# USB_OTG_FS.net
KiCad netlist of a schematic drawn in Altium Designer
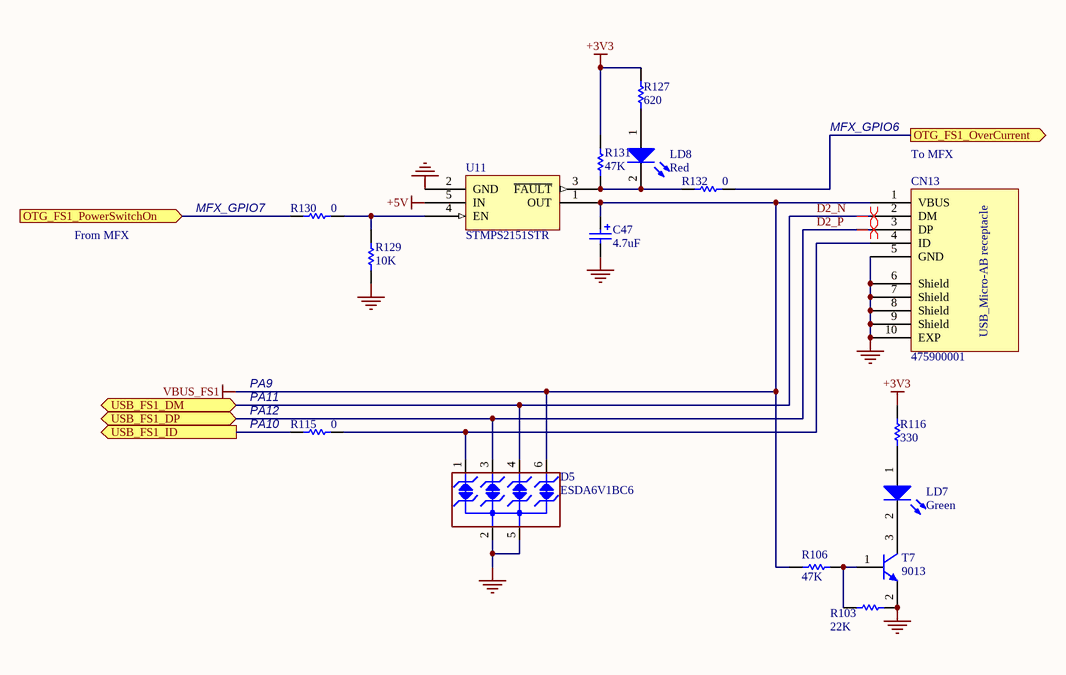
[diagram p0: USB_OTG_FS.SchDoc]

(export (version "E")
  (design (tool "Eeschema 10.0.6"))
  (components
    (comp (ref "C47")
      (value "4.7uF")
      (footprint "TAN-A")
      (description "Polarized Capacitor (Radial)")
      (fields (field (name "PUBLISHER") "Altium Limited"))
      (libsource (lib "Miscellaneous Devices") (part "Cap Pol1"))
    )
    (comp (ref "CN13")
      (value "475900001")
      (footprint "MOLEX_47590001")
      (libsource (lib "mb1045") (part "475900001"))
    )
    (comp (ref "D5")
      (value "ESDA6V1BC6")
      (footprint "SOT23-6")
      (description "Dual Transil array for ESD protection")
      (libsource (lib "MB1137") (part "ESDA6V1BC6"))
    )
    (comp (ref "LD7")
      (value "Green")
      (footprint "0603D")
      (description "Typical RED, GREEN, YELLOW, AMBER GaAs LED")
      (fields (field (name "PUBLISHER") "Altium Limited"))
      (libsource (lib "Miscellaneous Devices") (part "LED2"))
    )
    (comp (ref "LD8")
      (value "Red")
      (footprint "0603D")
      (description "Typical RED, GREEN, YELLOW, AMBER GaAs LED")
      (fields (field (name "PUBLISHER") "Altium Limited"))
      (libsource (lib "Miscellaneous Devices") (part "LED2"))
    )
    (comp (ref "R103")
      (value "22K")
      (footprint "0603R")
      (description "Resistor")
      (fields (field (name "PUBLISHER") "Altium Limited"))
      (libsource (lib "Miscellaneous Devices") (part "res1"))
    )
    (comp (ref "R106")
      (value "47K")
      (footprint "0603R")
      (description "Resistor")
      (fields (field (name "PUBLISHER") "Altium Limited"))
      (libsource (lib "Miscellaneous Devices") (part "res1"))
    )
    (comp (ref "R115")
      (value "0")
      (footprint "0603R")
      (description "Resistor")
      (fields (field (name "PUBLISHER") "Altium Limited"))
      (libsource (lib "Miscellaneous Devices") (part "Res1"))
    )
    (comp (ref "R116")
      (value "330")
      (footprint "0603R")
      (description "Resistor")
      (fields (field (name "PUBLISHER") "Altium Limited"))
      (libsource (lib "Miscellaneous Devices") (part "res1"))
    )
    (comp (ref "R127")
      (value "620")
      (footprint "0603R")
      (description "Resistor")
      (fields (field (name "PUBLISHER") "Altium Limited"))
      (libsource (lib "Miscellaneous Devices") (part "Res1"))
    )
    (comp (ref "R129")
      (value "10K")
      (footprint "0603R")
      (description "Resistor")
      (fields (field (name "PUBLISHER") "Altium Limited"))
      (libsource (lib "Miscellaneous Devices") (part "Res1"))
    )
    (comp (ref "R130")
      (value "0")
      (footprint "0603R")
      (description "Resistor")
      (fields (field (name "PUBLISHER") "Altium Limited"))
      (libsource (lib "Miscellaneous Devices") (part "Res1"))
    )
    (comp (ref "R131")
      (value "47K")
      (footprint "0603R")
      (description "Resistor")
      (fields (field (name "PUBLISHER") "Altium Limited"))
      (libsource (lib "Miscellaneous Devices") (part "res1"))
    )
    (comp (ref "R132")
      (value "0")
      (footprint "0603R")
      (description "Resistor")
      (fields (field (name "PUBLISHER") "Altium Limited"))
      (libsource (lib "Miscellaneous Devices") (part "Res1"))
    )
    (comp (ref "T7")
      (value "9013")
      (footprint "SOT-23")
      (description "NPN Bipolar Transistor")
      (fields (field (name "PUBLISHER") "Altium Limited"))
      (libsource (lib "MB1167") (part "NPN"))
    )
    (comp (ref "U11")
      (value "STMPS2151STR")
      (footprint "SOT23-5")
      (libsource (lib "mb1045") (part "STMPS2141STR"))
    )
  )
  (nets
    (net (code "1") (name "+3V3") (class "Default")
      (node (ref "R116") (pin "2") (pinfunction "2_2") (pintype "passive"))
      (node (ref "R127") (pin "2") (pinfunction "2_2") (pintype "passive"))
      (node (ref "R131") (pin "1") (pinfunction "1_1") (pintype "passive"))
    )
    (net (code "2") (name "+5V") (class "Default")
      (node (ref "U11") (pin "5") (pinfunction "IN_5") (pintype "passive"))
    )
    (net (code "3") (name "/D2_N") (class "Default")
      (node (ref "CN13") (pin "2") (pinfunction "DM_2") (pintype "passive"))
      (node (ref "D5") (pin "4") (pinfunction "IO3_4") (pintype "passive"))
    )
    (net (code "4") (name "/D2_P") (class "Default")
      (node (ref "CN13") (pin "3") (pinfunction "DP_3") (pintype "passive"))
      (node (ref "D5") (pin "3") (pinfunction "GND_3") (pintype "passive"))
    )
    (net (code "5") (name "/OTG_FS1_OverCurrent") (class "Default")
      (node (ref "R132") (pin "1") (pinfunction "1_1") (pintype "passive"))
    )
    (net (code "6") (name "/OTG_FS1_PowerSwitchOn") (class "Default")
      (node (ref "R130") (pin "2") (pinfunction "2_2") (pintype "passive"))
    )
    (net (code "7") (name "/USB_FS1_ID") (class "Default")
      (node (ref "R115") (pin "2") (pinfunction "2_2") (pintype "passive"))
    )
    (net (code "8") (name "GND") (class "Default")
      (node (ref "C47") (pin "2") (pinfunction "2_2") (pintype "passive"))
      (node (ref "CN13") (pin "10") (pinfunction "EXP_10") (pintype "passive"))
      (node (ref "CN13") (pin "5") (pinfunction "GND_5") (pintype "passive"))
      (node (ref "CN13") (pin "6") (pinfunction "Shield_6") (pintype "passive"))
      (node (ref "CN13") (pin "7") (pinfunction "Shield_7") (pintype "passive"))
      (node (ref "CN13") (pin "8") (pinfunction "Shield_8") (pintype "passive"))
      (node (ref "CN13") (pin "9") (pinfunction "Shield_9") (pintype "passive"))
      (node (ref "D5") (pin "2") (pinfunction "IO2_2") (pintype "passive"))
      (node (ref "D5") (pin "5") (pinfunction "IO4_5") (pintype "passive"))
      (node (ref "R103") (pin "1") (pinfunction "1_1") (pintype "passive"))
      (node (ref "R129") (pin "1") (pinfunction "1_1") (pintype "passive"))
      (node (ref "T7") (pin "2") (pinfunction "E_2") (pintype "passive"))
      (node (ref "U11") (pin "2") (pinfunction "GND_2") (pintype "passive"))
    )
    (net (code "9") (name "Net-(CN13-ID)") (class "Default")
      (node (ref "CN13") (pin "4") (pinfunction "ID_4") (pintype "passive"))
      (node (ref "D5") (pin "1") (pinfunction "IO1_1") (pintype "passive"))
      (node (ref "R115") (pin "1") (pinfunction "1_1") (pintype "passive"))
    )
    (net (code "10") (name "Net-(LD7-A)") (class "Default")
      (node (ref "LD7") (pin "1") (pinfunction "A_1") (pintype "passive"))
      (node (ref "R116") (pin "1") (pinfunction "1_1") (pintype "passive"))
    )
    (net (code "11") (name "Net-(LD7-K)") (class "Default")
      (node (ref "LD7") (pin "2") (pinfunction "K_2") (pintype "passive"))
      (node (ref "T7") (pin "3") (pinfunction "C_3") (pintype "passive"))
    )
    (net (code "12") (name "Net-(LD8-A)") (class "Default")
      (node (ref "LD8") (pin "1") (pinfunction "A_1") (pintype "passive"))
      (node (ref "R127") (pin "1") (pinfunction "1_1") (pintype "passive"))
    )
    (net (code "13") (name "Net-(LD8-K)") (class "Default")
      (node (ref "LD8") (pin "2") (pinfunction "K_2") (pintype "passive"))
      (node (ref "R131") (pin "2") (pinfunction "2_2") (pintype "passive"))
      (node (ref "R132") (pin "2") (pinfunction "2_2") (pintype "passive"))
      (node (ref "U11") (pin "3") (pinfunction "~{FAULT}_3") (pintype "output"))
    )
    (net (code "14") (name "Net-(T7-B)") (class "Default")
      (node (ref "R103") (pin "2") (pinfunction "2_2") (pintype "passive"))
      (node (ref "R106") (pin "2") (pinfunction "2_2") (pintype "passive"))
      (node (ref "T7") (pin "1") (pinfunction "B_1") (pintype "passive"))
    )
    (net (code "15") (name "Net-(U11-EN)") (class "Default")
      (node (ref "R129") (pin "2") (pinfunction "2_2") (pintype "passive"))
      (node (ref "R130") (pin "1") (pinfunction "1_1") (pintype "passive"))
      (node (ref "U11") (pin "4") (pinfunction "EN_4") (pintype "input"))
    )
    (net (code "16") (name "VBUS_FS1") (class "Default")
      (node (ref "C47") (pin "1") (pinfunction "1_1") (pintype "passive"))
      (node (ref "CN13") (pin "1") (pinfunction "VBUS_1") (pintype "passive"))
      (node (ref "D5") (pin "6") (pinfunction "NC_6") (pintype "passive"))
      (node (ref "R106") (pin "1") (pinfunction "1_1") (pintype "passive"))
      (node (ref "U11") (pin "1") (pinfunction "OUT_1") (pintype "passive"))
    )
  )
)
